# cinch_stereo_ingang.net
KiCad netlist of a schematic drawn in Altium Designer
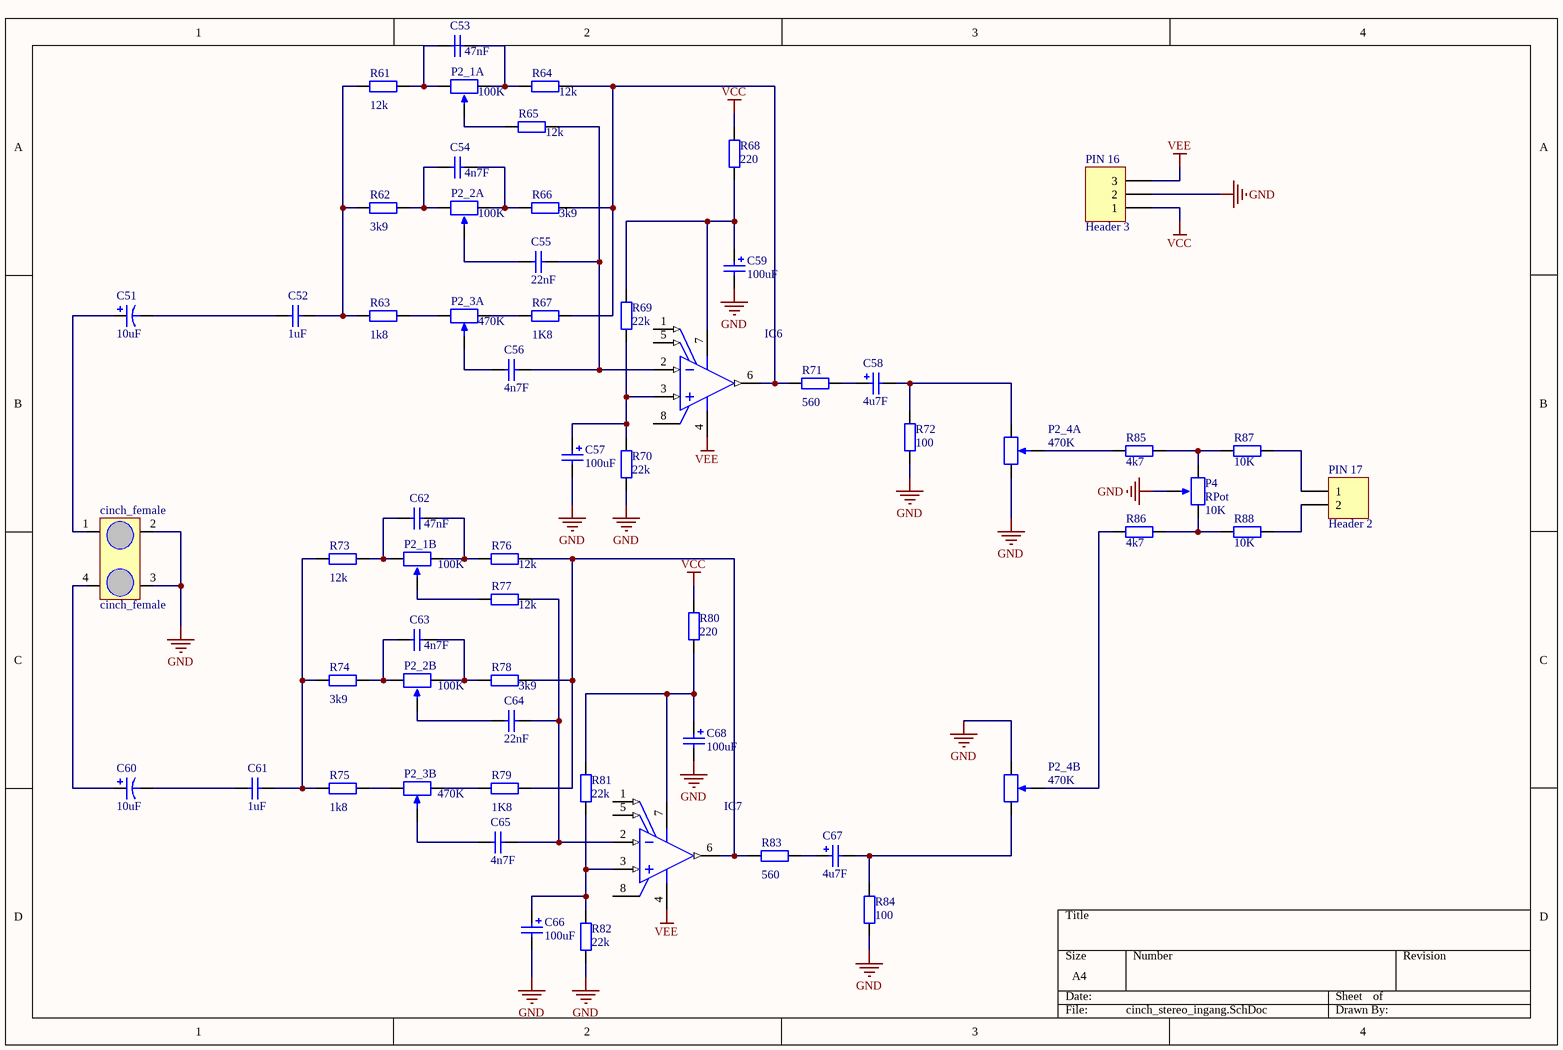
[diagram p0: cinch_stereo_ingang.SchDoc]

(export (version "E")
  (design (tool "Eeschema 10.0.6"))
  (components
    (comp (ref "C51")
      (value "10uF")
      (footprint "Capacitor 10uF")
      (description "electrolytic")
      (fields (field (name "Comment") "Cap Pol2") (field (name "PUBLISHER") "Altium Limited"))
      (libsource (lib "") (part "Cap Pol2_1"))
    )
    (comp (ref "C52")
      (value "1uF")
      (footprint "Capacitor 1uF")
      (description "Capacitor")
      (fields (field (name "Comment") "Cap") (field (name "PUBLISHER") "Altium Limited"))
      (libsource (lib "Autio_Mixer") (part "Cap"))
    )
    (comp (ref "C53")
      (value "47nF")
      (footprint "Capacitor 22nF, 47nF, 100nF")
      (description "Capacitor")
      (fields (field (name "Comment") "Cap") (field (name "PUBLISHER") "Altium Limited"))
      (libsource (lib "Autio_Mixer") (part "Cap"))
    )
    (comp (ref "C54")
      (value "4n7F")
      (footprint "Capacitor 22nF, 47nF, 100nF")
      (description "Capacitor")
      (fields (field (name "Comment") "Cap") (field (name "PUBLISHER") "Altium Limited"))
      (libsource (lib "Autio_Mixer") (part "Cap"))
    )
    (comp (ref "C55")
      (value "22nF")
      (footprint "Capacitor 22nF, 47nF, 100nF")
      (description "Capacitor")
      (fields (field (name "Comment") "Cap") (field (name "PUBLISHER") "Altium Limited"))
      (libsource (lib "Autio_Mixer") (part "Cap"))
    )
    (comp (ref "C56")
      (value "4n7F")
      (footprint "Capacitor 22nF, 47nF, 100nF")
      (description "Capacitor")
      (fields (field (name "Comment") "Cap") (field (name "PUBLISHER") "Altium Limited"))
      (libsource (lib "Autio_Mixer") (part "Cap"))
    )
    (comp (ref "C57")
      (value "100uF")
      (footprint "Capacitor 100uF")
      (description "electrolytic")
      (fields (field (name "Comment") "Cap Pol2") (field (name "PUBLISHER") "Altium Limited"))
      (libsource (lib "Autio_Mixer") (part "Cap Pol2"))
    )
    (comp (ref "C58")
      (value "4u7F")
      (footprint "Capacitor 4u7F")
      (description "electrolytic")
      (fields (field (name "Comment") "Cap Pol2") (field (name "PUBLISHER") "Altium Limited"))
      (libsource (lib "Autio_Mixer") (part "Cap Pol2"))
    )
    (comp (ref "C59")
      (value "100uF")
      (footprint "Capacitor 100uF")
      (description "electrolytic")
      (fields (field (name "Comment") "Cap Pol2") (field (name "PUBLISHER") "Altium Limited"))
      (libsource (lib "Autio_Mixer") (part "Cap Pol2"))
    )
    (comp (ref "C60")
      (value "10uF")
      (footprint "Capacitor 10uF")
      (description "electrolytic")
      (fields (field (name "Comment") "Cap Pol2") (field (name "PUBLISHER") "Altium Limited"))
      (libsource (lib "") (part "Cap Pol2_1"))
    )
    (comp (ref "C61")
      (value "1uF")
      (footprint "Capacitor 1uF")
      (description "Capacitor")
      (fields (field (name "Comment") "Cap") (field (name "PUBLISHER") "Altium Limited"))
      (libsource (lib "Autio_Mixer") (part "Cap"))
    )
    (comp (ref "C62")
      (value "47nF")
      (footprint "Capacitor 22nF, 47nF, 100nF")
      (description "Capacitor")
      (fields (field (name "Comment") "Cap") (field (name "PUBLISHER") "Altium Limited"))
      (libsource (lib "Autio_Mixer") (part "Cap"))
    )
    (comp (ref "C63")
      (value "4n7F")
      (footprint "Capacitor 22nF, 47nF, 100nF")
      (description "Capacitor")
      (fields (field (name "Comment") "Cap") (field (name "PUBLISHER") "Altium Limited"))
      (libsource (lib "Autio_Mixer") (part "Cap"))
    )
    (comp (ref "C64")
      (value "22nF")
      (footprint "Capacitor 22nF, 47nF, 100nF")
      (description "Capacitor")
      (fields (field (name "Comment") "Cap") (field (name "PUBLISHER") "Altium Limited"))
      (libsource (lib "Autio_Mixer") (part "Cap"))
    )
    (comp (ref "C65")
      (value "4n7F")
      (footprint "Capacitor 22nF, 47nF, 100nF")
      (description "Capacitor")
      (fields (field (name "Comment") "Cap") (field (name "PUBLISHER") "Altium Limited"))
      (libsource (lib "Autio_Mixer") (part "Cap"))
    )
    (comp (ref "C66")
      (value "100uF")
      (footprint "Capacitor 100uF")
      (description "electrolytic")
      (fields (field (name "Comment") "Cap Pol2") (field (name "PUBLISHER") "Altium Limited"))
      (libsource (lib "Autio_Mixer") (part "Cap Pol2"))
    )
    (comp (ref "C67")
      (value "4u7F")
      (footprint "Capacitor 4u7F")
      (description "electrolytic")
      (fields (field (name "Comment") "Cap Pol2") (field (name "PUBLISHER") "Altium Limited"))
      (libsource (lib "Autio_Mixer") (part "Cap Pol2"))
    )
    (comp (ref "C68")
      (value "100uF")
      (footprint "Capacitor 100uF")
      (description "electrolytic")
      (fields (field (name "Comment") "Cap Pol2") (field (name "PUBLISHER") "Altium Limited"))
      (libsource (lib "Autio_Mixer") (part "Cap Pol2"))
    )
    (comp (ref "cinch_female")
      (value "cinch_female")
      (footprint "header_4")
      (libsource (lib "Autio_Mixer") (part "cinch_female"))
    )
    (comp (ref "IC6")
      (value "TL061CD")
      (footprint "OPAMP_TL061")
      (fields (field (name "MANUFACTURER") "Texas Instruments"))
      (libsource (lib "Autio_Mixer") (part "opamp_TL061"))
    )
    (comp (ref "IC7")
      (value "TL061CD")
      (footprint "OPAMP_TL061")
      (fields (field (name "MANUFACTURER") "Texas Instruments"))
      (libsource (lib "Autio_Mixer") (part "opamp_TL061"))
    )
    (comp (ref "P2_1A")
      (value "100K")
      (footprint "header_3")
      (description "Potentiometer")
      (fields (field (name "Comment") "RPot") (field (name "PUBLISHER") "Altium Limited"))
      (libsource (lib "Autio_Mixer") (part "RPot"))
    )
    (comp (ref "P2_1B")
      (value "100K")
      (footprint "header_3")
      (description "Potentiometer")
      (fields (field (name "Comment") "RPot") (field (name "PUBLISHER") "Altium Limited"))
      (libsource (lib "Autio_Mixer") (part "RPot"))
    )
    (comp (ref "P2_2A")
      (value "100K")
      (footprint "header_3")
      (description "Potentiometer")
      (fields (field (name "Comment") "RPot") (field (name "PUBLISHER") "Altium Limited"))
      (libsource (lib "Autio_Mixer") (part "RPot"))
    )
    (comp (ref "P2_2B")
      (value "100K")
      (footprint "header_3")
      (description "Potentiometer")
      (fields (field (name "Comment") "RPot") (field (name "PUBLISHER") "Altium Limited"))
      (libsource (lib "Autio_Mixer") (part "RPot"))
    )
    (comp (ref "P2_3A")
      (value "470K")
      (footprint "header_3")
      (description "Potentiometer")
      (fields (field (name "Comment") "RPot") (field (name "PUBLISHER") "Altium Limited"))
      (libsource (lib "") (part "RPot_1_1"))
    )
    (comp (ref "P2_3B")
      (value "470K")
      (footprint "header_3")
      (description "Potentiometer")
      (fields (field (name "Comment") "RPot") (field (name "PUBLISHER") "Altium Limited"))
      (libsource (lib "") (part "RPot_1_1"))
    )
    (comp (ref "P2_4A")
      (value "470K")
      (footprint "header_3")
      (description "Potentiometer")
      (fields (field (name "Comment") "RPot") (field (name "PUBLISHER") "Altium Limited"))
      (libsource (lib "") (part "RPot_1_2"))
    )
    (comp (ref "P2_4B")
      (value "470K")
      (footprint "header_3")
      (description "Potentiometer")
      (fields (field (name "Comment") "RPot") (field (name "PUBLISHER") "Altium Limited"))
      (libsource (lib "Autio_Mixer") (part "RPot_1"))
    )
    (comp (ref "P4")
      (value "RPot")
      (footprint "header_3")
      (description "Potentiometer")
      (fields (field (name "ALTIUM_VALUE") "10K") (field (name "PUBLISHER") "Altium Limited"))
      (libsource (lib "") (part "RPot_1"))
    )
    (comp (ref "PIN 16")
      (value "Header 3")
      (footprint "header_3")
      (description "Header, 3-Pin")
      (fields (field (name "PUBLISHER") "Altium Limited"))
      (libsource (lib "Miscellaneous Connectors") (part "Header 3"))
    )
    (comp (ref "PIN 17")
      (value "Header 2")
      (footprint "header_2")
      (description "Header, 2-Pin")
      (fields (field (name "PUBLISHER") "Altium Limited"))
      (libsource (lib "Miscellaneous Connectors") (part "Header 2"))
    )
    (comp (ref "R61")
      (value "12k")
      (footprint "C1206")
      (description "Resistor")
      (fields (field (name "Comment") "Res2") (field (name "PUBLISHER") "Altium Limited"))
      (libsource (lib "") (part "Res2_1"))
    )
    (comp (ref "R62")
      (value "3k9")
      (footprint "C1206")
      (description "Resistor")
      (fields (field (name "Comment") "Res2") (field (name "PUBLISHER") "Altium Limited"))
      (libsource (lib "") (part "Res2_1"))
    )
    (comp (ref "R63")
      (value "1k8")
      (footprint "C1206")
      (description "Resistor")
      (fields (field (name "Comment") "Res2") (field (name "PUBLISHER") "Altium Limited"))
      (libsource (lib "") (part "Res2_1"))
    )
    (comp (ref "R64")
      (value "12k")
      (footprint "C1206")
      (description "Resistor")
      (fields (field (name "Comment") "Res2") (field (name "PUBLISHER") "Altium Limited"))
      (libsource (lib "") (part "Res2_1"))
    )
    (comp (ref "R65")
      (value "12k")
      (footprint "C1206")
      (description "Resistor")
      (fields (field (name "Comment") "Res2") (field (name "PUBLISHER") "Altium Limited"))
      (libsource (lib "") (part "Res2_1"))
    )
    (comp (ref "R66")
      (value "3k9")
      (footprint "C1206")
      (description "Resistor")
      (fields (field (name "Comment") "Res2") (field (name "PUBLISHER") "Altium Limited"))
      (libsource (lib "") (part "Res2_1"))
    )
    (comp (ref "R67")
      (value "1K8")
      (footprint "C1206")
      (description "Resistor")
      (fields (field (name "Comment") "Res2") (field (name "PUBLISHER") "Altium Limited"))
      (libsource (lib "") (part "Res2_1"))
    )
    (comp (ref "R68")
      (value "220")
      (footprint "C1206")
      (description "Resistor")
      (fields (field (name "Comment") "Res2") (field (name "PUBLISHER") "Altium Limited"))
      (libsource (lib "Miscellaneous Devices") (part "Res2"))
    )
    (comp (ref "R69")
      (value "22k")
      (footprint "C1206")
      (description "Resistor")
      (fields (field (name "Comment") "Res2") (field (name "PUBLISHER") "Altium Limited"))
      (libsource (lib "Miscellaneous Devices") (part "Res2"))
    )
    (comp (ref "R70")
      (value "22k")
      (footprint "C1206")
      (description "Resistor")
      (fields (field (name "Comment") "Res2") (field (name "PUBLISHER") "Altium Limited"))
      (libsource (lib "Miscellaneous Devices") (part "Res2"))
    )
    (comp (ref "R71")
      (value "560")
      (footprint "C1206")
      (description "Resistor")
      (fields (field (name "Comment") "Res2") (field (name "PUBLISHER") "Altium Limited"))
      (libsource (lib "") (part "Res2_1"))
    )
    (comp (ref "R72")
      (value "100")
      (footprint "C1206")
      (description "Resistor")
      (fields (field (name "Comment") "Res2") (field (name "PUBLISHER") "Altium Limited"))
      (libsource (lib "Miscellaneous Devices") (part "Res2"))
    )
    (comp (ref "R73")
      (value "12k")
      (footprint "C1206")
      (description "Resistor")
      (fields (field (name "Comment") "Res2") (field (name "PUBLISHER") "Altium Limited"))
      (libsource (lib "") (part "Res2_1"))
    )
    (comp (ref "R74")
      (value "3k9")
      (footprint "C1206")
      (description "Resistor")
      (fields (field (name "Comment") "Res2") (field (name "PUBLISHER") "Altium Limited"))
      (libsource (lib "") (part "Res2_1"))
    )
    (comp (ref "R75")
      (value "1k8")
      (footprint "C1206")
      (description "Resistor")
      (fields (field (name "Comment") "Res2") (field (name "PUBLISHER") "Altium Limited"))
      (libsource (lib "") (part "Res2_1"))
    )
    (comp (ref "R76")
      (value "12k")
      (footprint "C1206")
      (description "Resistor")
      (fields (field (name "Comment") "Res2") (field (name "PUBLISHER") "Altium Limited"))
      (libsource (lib "") (part "Res2_1"))
    )
    (comp (ref "R77")
      (value "12k")
      (footprint "C1206")
      (description "Resistor")
      (fields (field (name "Comment") "Res2") (field (name "PUBLISHER") "Altium Limited"))
      (libsource (lib "") (part "Res2_1"))
    )
    (comp (ref "R78")
      (value "3k9")
      (footprint "C1206")
      (description "Resistor")
      (fields (field (name "Comment") "Res2") (field (name "PUBLISHER") "Altium Limited"))
      (libsource (lib "") (part "Res2_1"))
    )
    (comp (ref "R79")
      (value "1K8")
      (footprint "C1206")
      (description "Resistor")
      (fields (field (name "Comment") "Res2") (field (name "PUBLISHER") "Altium Limited"))
      (libsource (lib "") (part "Res2_1"))
    )
    (comp (ref "R80")
      (value "220")
      (footprint "C1206")
      (description "Resistor")
      (fields (field (name "Comment") "Res2") (field (name "PUBLISHER") "Altium Limited"))
      (libsource (lib "Miscellaneous Devices") (part "Res2"))
    )
    (comp (ref "R81")
      (value "22k")
      (footprint "C1206")
      (description "Resistor")
      (fields (field (name "Comment") "Res2") (field (name "PUBLISHER") "Altium Limited"))
      (libsource (lib "Miscellaneous Devices") (part "Res2"))
    )
    (comp (ref "R82")
      (value "22k")
      (footprint "C1206")
      (description "Resistor")
      (fields (field (name "Comment") "Res2") (field (name "PUBLISHER") "Altium Limited"))
      (libsource (lib "Miscellaneous Devices") (part "Res2"))
    )
    (comp (ref "R83")
      (value "560")
      (footprint "C1206")
      (description "Resistor")
      (fields (field (name "Comment") "Res2") (field (name "PUBLISHER") "Altium Limited"))
      (libsource (lib "") (part "Res2_1"))
    )
    (comp (ref "R84")
      (value "100")
      (footprint "C1206")
      (description "Resistor")
      (fields (field (name "Comment") "Res2") (field (name "PUBLISHER") "Altium Limited"))
      (libsource (lib "Miscellaneous Devices") (part "Res2"))
    )
    (comp (ref "R85")
      (value "4k7")
      (footprint "C1206")
      (description "Resistor")
      (fields (field (name "Comment") "Res2") (field (name "PUBLISHER") "Altium Limited"))
      (libsource (lib "Autio_Mixer") (part "Res2_13"))
    )
    (comp (ref "R86")
      (value "4k7")
      (footprint "C1206")
      (description "Resistor")
      (fields (field (name "Comment") "Res2") (field (name "PUBLISHER") "Altium Limited"))
      (libsource (lib "Autio_Mixer") (part "Res2_13"))
    )
    (comp (ref "R87")
      (value "10K")
      (footprint "C1206")
      (description "Resistor")
      (fields (field (name "Comment") "Res2") (field (name "PUBLISHER") "Altium Limited"))
      (libsource (lib "Autio_Mixer") (part "Res2_3"))
    )
    (comp (ref "R88")
      (value "10K")
      (footprint "C1206")
      (description "Resistor")
      (fields (field (name "Comment") "Res2") (field (name "PUBLISHER") "Altium Limited"))
      (libsource (lib "Autio_Mixer") (part "Res2_3"))
    )
  )
  (nets
    (net (code "1") (name "GND") (class "Default")
      (node (ref "C57") (pin "2") (pinfunction "2_2") (pintype "passive"))
      (node (ref "C59") (pin "2") (pinfunction "2_2") (pintype "passive"))
      (node (ref "C66") (pin "2") (pinfunction "2_2") (pintype "passive"))
      (node (ref "C68") (pin "2") (pinfunction "2_2") (pintype "passive"))
      (node (ref "P2_4A") (pin "3") (pinfunction "TOP_3") (pintype "passive"))
      (node (ref "P2_4B") (pin "3") (pinfunction "BOT_3") (pintype "passive"))
      (node (ref "P4") (pin "3") (pinfunction "TAP_3") (pintype "passive"))
      (node (ref "PIN 16") (pin "3") (pinfunction "2_3") (pintype "passive"))
      (node (ref "R70") (pin "1") (pinfunction "1_1") (pintype "passive"))
      (node (ref "R72") (pin "1") (pinfunction "1_1") (pintype "passive"))
      (node (ref "R82") (pin "1") (pinfunction "1_1") (pintype "passive"))
      (node (ref "R84") (pin "1") (pinfunction "1_1") (pintype "passive"))
      (node (ref "cinch_female") (pin "2") (pinfunction "GND_left_2") (pintype "passive"))
      (node (ref "cinch_female") (pin "3") (pinfunction "GND_right_3") (pintype "passive"))
    )
    (net (code "2") (name "Net-(C51-Pad2)") (class "Default")
      (node (ref "C51") (pin "2") (pinfunction "2_2") (pintype "passive"))
      (node (ref "C52") (pin "1") (pinfunction "1_1") (pintype "passive"))
    )
    (net (code "3") (name "Net-(C52-Pad2)") (class "Default")
      (node (ref "C52") (pin "2") (pinfunction "2_2") (pintype "passive"))
      (node (ref "R61") (pin "1") (pinfunction "1_1") (pintype "passive"))
      (node (ref "R62") (pin "1") (pinfunction "1_1") (pintype "passive"))
      (node (ref "R63") (pin "1") (pinfunction "1_1") (pintype "passive"))
    )
    (net (code "4") (name "Net-(C58-Pad1)") (class "Default")
      (node (ref "C58") (pin "1") (pinfunction "1_1") (pintype "passive"))
      (node (ref "R71") (pin "2") (pinfunction "2_2") (pintype "passive"))
    )
    (net (code "5") (name "Net-(C60-Pad2)") (class "Default")
      (node (ref "C60") (pin "2") (pinfunction "2_2") (pintype "passive"))
      (node (ref "C61") (pin "1") (pinfunction "1_1") (pintype "passive"))
    )
    (net (code "6") (name "Net-(C61-Pad2)") (class "Default")
      (node (ref "C61") (pin "2") (pinfunction "2_2") (pintype "passive"))
      (node (ref "R73") (pin "1") (pinfunction "1_1") (pintype "passive"))
      (node (ref "R74") (pin "1") (pinfunction "1_1") (pintype "passive"))
      (node (ref "R75") (pin "1") (pinfunction "1_1") (pintype "passive"))
    )
    (net (code "7") (name "Net-(C67-Pad1)") (class "Default")
      (node (ref "C67") (pin "1") (pinfunction "1_1") (pintype "passive"))
      (node (ref "R83") (pin "2") (pinfunction "2_2") (pintype "passive"))
    )
    (net (code "8") (name "Net-(IC6-IN+)") (class "Default")
      (node (ref "C57") (pin "1") (pinfunction "1_1") (pintype "passive"))
      (node (ref "IC6") (pin "3") (pinfunction "IN+_3") (pintype "input"))
      (node (ref "R69") (pin "1") (pinfunction "1_1") (pintype "passive"))
      (node (ref "R70") (pin "2") (pinfunction "2_2") (pintype "passive"))
    )
    (net (code "9") (name "Net-(IC6-IN-)") (class "Default")
      (node (ref "C55") (pin "2") (pinfunction "2_2") (pintype "passive"))
      (node (ref "C56") (pin "2") (pinfunction "2_2") (pintype "passive"))
      (node (ref "IC6") (pin "2") (pinfunction "IN-_2") (pintype "input"))
      (node (ref "R65") (pin "2") (pinfunction "2_2") (pintype "passive"))
    )
    (net (code "10") (name "Net-(IC6-OUT)") (class "Default")
      (node (ref "IC6") (pin "6") (pinfunction "OUT_6") (pintype "output"))
      (node (ref "R64") (pin "2") (pinfunction "2_2") (pintype "passive"))
      (node (ref "R66") (pin "2") (pinfunction "2_2") (pintype "passive"))
      (node (ref "R67") (pin "2") (pinfunction "2_2") (pintype "passive"))
      (node (ref "R71") (pin "1") (pinfunction "1_1") (pintype "passive"))
    )
    (net (code "11") (name "Net-(IC6-VCC+)") (class "Default")
      (node (ref "C59") (pin "1") (pinfunction "1_1") (pintype "passive"))
      (node (ref "IC6") (pin "7") (pinfunction "VCC+_7") (pintype "power_in"))
      (node (ref "R68") (pin "1") (pinfunction "1_1") (pintype "passive"))
      (node (ref "R69") (pin "2") (pinfunction "2_2") (pintype "passive"))
    )
    (net (code "12") (name "Net-(IC7-IN+)") (class "Default")
      (node (ref "C66") (pin "1") (pinfunction "1_1") (pintype "passive"))
      (node (ref "IC7") (pin "3") (pinfunction "IN+_3") (pintype "input"))
      (node (ref "R81") (pin "1") (pinfunction "1_1") (pintype "passive"))
      (node (ref "R82") (pin "2") (pinfunction "2_2") (pintype "passive"))
    )
    (net (code "13") (name "Net-(IC7-IN-)") (class "Default")
      (node (ref "C64") (pin "2") (pinfunction "2_2") (pintype "passive"))
      (node (ref "C65") (pin "2") (pinfunction "2_2") (pintype "passive"))
      (node (ref "IC7") (pin "2") (pinfunction "IN-_2") (pintype "input"))
      (node (ref "R77") (pin "2") (pinfunction "2_2") (pintype "passive"))
    )
    (net (code "14") (name "Net-(IC7-OUT)") (class "Default")
      (node (ref "IC7") (pin "6") (pinfunction "OUT_6") (pintype "output"))
      (node (ref "R76") (pin "2") (pinfunction "2_2") (pintype "passive"))
      (node (ref "R78") (pin "2") (pinfunction "2_2") (pintype "passive"))
      (node (ref "R79") (pin "2") (pinfunction "2_2") (pintype "passive"))
      (node (ref "R83") (pin "1") (pinfunction "1_1") (pintype "passive"))
    )
    (net (code "15") (name "Net-(IC7-VCC+)") (class "Default")
      (node (ref "C68") (pin "1") (pinfunction "1_1") (pintype "passive"))
      (node (ref "IC7") (pin "7") (pinfunction "VCC+_7") (pintype "power_in"))
      (node (ref "R80") (pin "1") (pinfunction "1_1") (pintype "passive"))
      (node (ref "R81") (pin "2") (pinfunction "2_2") (pintype "passive"))
    )
    (net (code "16") (name "Net-(P2_1A-BOT)") (class "Default")
      (node (ref "C53") (pin "2") (pinfunction "2_2") (pintype "passive"))
      (node (ref "P2_1A") (pin "3") (pinfunction "BOT_3") (pintype "passive"))
      (node (ref "R64") (pin "1") (pinfunction "1_1") (pintype "passive"))
    )
    (net (code "17") (name "Net-(P2_1A-TAP)") (class "Default")
      (node (ref "P2_1A") (pin "2") (pinfunction "TAP_2") (pintype "passive"))
      (node (ref "R65") (pin "1") (pinfunction "1_1") (pintype "passive"))
    )
    (net (code "18") (name "Net-(P2_1A-TOP)") (class "Default")
      (node (ref "C53") (pin "1") (pinfunction "1_1") (pintype "passive"))
      (node (ref "P2_1A") (pin "1") (pinfunction "TOP_1") (pintype "passive"))
      (node (ref "R61") (pin "2") (pinfunction "2_2") (pintype "passive"))
    )
    (net (code "19") (name "Net-(P2_1B-BOT)") (class "Default")
      (node (ref "C62") (pin "2") (pinfunction "2_2") (pintype "passive"))
      (node (ref "P2_1B") (pin "3") (pinfunction "BOT_3") (pintype "passive"))
      (node (ref "R76") (pin "1") (pinfunction "1_1") (pintype "passive"))
    )
    (net (code "20") (name "Net-(P2_1B-TAP)") (class "Default")
      (node (ref "P2_1B") (pin "2") (pinfunction "TAP_2") (pintype "passive"))
      (node (ref "R77") (pin "1") (pinfunction "1_1") (pintype "passive"))
    )
    (net (code "21") (name "Net-(P2_1B-TOP)") (class "Default")
      (node (ref "C62") (pin "1") (pinfunction "1_1") (pintype "passive"))
      (node (ref "P2_1B") (pin "1") (pinfunction "TOP_1") (pintype "passive"))
      (node (ref "R73") (pin "2") (pinfunction "2_2") (pintype "passive"))
    )
    (net (code "22") (name "Net-(P2_2A-BOT)") (class "Default")
      (node (ref "C54") (pin "2") (pinfunction "2_2") (pintype "passive"))
      (node (ref "P2_2A") (pin "3") (pinfunction "BOT_3") (pintype "passive"))
      (node (ref "R66") (pin "1") (pinfunction "1_1") (pintype "passive"))
    )
    (net (code "23") (name "Net-(P2_2A-TAP)") (class "Default")
      (node (ref "C55") (pin "1") (pinfunction "1_1") (pintype "passive"))
      (node (ref "P2_2A") (pin "2") (pinfunction "TAP_2") (pintype "passive"))
    )
    (net (code "24") (name "Net-(P2_2A-TOP)") (class "Default")
      (node (ref "C54") (pin "1") (pinfunction "1_1") (pintype "passive"))
      (node (ref "P2_2A") (pin "1") (pinfunction "TOP_1") (pintype "passive"))
      (node (ref "R62") (pin "2") (pinfunction "2_2") (pintype "passive"))
    )
    (net (code "25") (name "Net-(P2_2B-BOT)") (class "Default")
      (node (ref "C63") (pin "2") (pinfunction "2_2") (pintype "passive"))
      (node (ref "P2_2B") (pin "3") (pinfunction "BOT_3") (pintype "passive"))
      (node (ref "R78") (pin "1") (pinfunction "1_1") (pintype "passive"))
    )
    (net (code "26") (name "Net-(P2_2B-TAP)") (class "Default")
      (node (ref "C64") (pin "1") (pinfunction "1_1") (pintype "passive"))
      (node (ref "P2_2B") (pin "2") (pinfunction "TAP_2") (pintype "passive"))
    )
    (net (code "27") (name "Net-(P2_2B-TOP)") (class "Default")
      (node (ref "C63") (pin "1") (pinfunction "1_1") (pintype "passive"))
      (node (ref "P2_2B") (pin "1") (pinfunction "TOP_1") (pintype "passive"))
      (node (ref "R74") (pin "2") (pinfunction "2_2") (pintype "passive"))
    )
    (net (code "28") (name "Net-(P2_3A-BOT)") (class "Default")
      (node (ref "P2_3A") (pin "3") (pinfunction "BOT_3") (pintype "passive"))
      (node (ref "R67") (pin "1") (pinfunction "1_1") (pintype "passive"))
    )
    (net (code "29") (name "Net-(P2_3A-TAP)") (class "Default")
      (node (ref "C56") (pin "1") (pinfunction "1_1") (pintype "passive"))
      (node (ref "P2_3A") (pin "2") (pinfunction "TAP_2") (pintype "passive"))
    )
    (net (code "30") (name "Net-(P2_3A-TOP)") (class "Default")
      (node (ref "P2_3A") (pin "1") (pinfunction "TOP_1") (pintype "passive"))
      (node (ref "R63") (pin "2") (pinfunction "2_2") (pintype "passive"))
    )
    (net (code "31") (name "Net-(P2_3B-BOT)") (class "Default")
      (node (ref "P2_3B") (pin "3") (pinfunction "BOT_3") (pintype "passive"))
      (node (ref "R79") (pin "1") (pinfunction "1_1") (pintype "passive"))
    )
    (net (code "32") (name "Net-(P2_3B-TAP)") (class "Default")
      (node (ref "C65") (pin "1") (pinfunction "1_1") (pintype "passive"))
      (node (ref "P2_3B") (pin "2") (pinfunction "TAP_2") (pintype "passive"))
    )
    (net (code "33") (name "Net-(P2_3B-TOP)") (class "Default")
      (node (ref "P2_3B") (pin "1") (pinfunction "TOP_1") (pintype "passive"))
      (node (ref "R75") (pin "2") (pinfunction "2_2") (pintype "passive"))
    )
    (net (code "34") (name "Net-(P2_4A-BOT)") (class "Default")
      (node (ref "C58") (pin "2") (pinfunction "2_2") (pintype "passive"))
      (node (ref "P2_4A") (pin "1") (pinfunction "BOT_1") (pintype "passive"))
      (node (ref "R72") (pin "2") (pinfunction "2_2") (pintype "passive"))
    )
    (net (code "35") (name "Net-(P2_4A-TAP)") (class "Default")
      (node (ref "P2_4A") (pin "2") (pinfunction "TAP_2") (pintype "passive"))
      (node (ref "R85") (pin "1") (pinfunction "1_1") (pintype "passive"))
    )
    (net (code "36") (name "Net-(P2_4B-TAP)") (class "Default")
      (node (ref "P2_4B") (pin "2") (pinfunction "TAP_2") (pintype "passive"))
      (node (ref "R86") (pin "1") (pinfunction "1_1") (pintype "passive"))
    )
    (net (code "37") (name "Net-(P2_4B-TOP)") (class "Default")
      (node (ref "C67") (pin "2") (pinfunction "2_2") (pintype "passive"))
      (node (ref "P2_4B") (pin "1") (pinfunction "TOP_1") (pintype "passive"))
      (node (ref "R84") (pin "2") (pinfunction "2_2") (pintype "passive"))
    )
    (net (code "38") (name "Net-(P4-BOT)") (class "Default")
      (node (ref "P4") (pin "1") (pinfunction "BOT_1") (pintype "passive"))
      (node (ref "R86") (pin "2") (pinfunction "2_2") (pintype "passive"))
      (node (ref "R88") (pin "1") (pinfunction "1_1") (pintype "passive"))
    )
    (net (code "39") (name "Net-(P4-TOP)") (class "Default")
      (node (ref "P4") (pin "2") (pinfunction "TOP_2") (pintype "passive"))
      (node (ref "R85") (pin "2") (pinfunction "2_2") (pintype "passive"))
      (node (ref "R87") (pin "1") (pinfunction "1_1") (pintype "passive"))
    )
    (net (code "40") (name "Net-(PIN 17-Pad1)") (class "Default")
      (node (ref "PIN 17") (pin "1") (pinfunction "1_1") (pintype "passive"))
      (node (ref "R87") (pin "2") (pinfunction "2_2") (pintype "passive"))
    )
    (net (code "41") (name "Net-(PIN 17-Pad2)") (class "Default")
      (node (ref "PIN 17") (pin "2") (pinfunction "2_2") (pintype "passive"))
      (node (ref "R88") (pin "2") (pinfunction "2_2") (pintype "passive"))
    )
    (net (code "42") (name "Net-(cinch_female-Left_red)") (class "Default")
      (node (ref "C51") (pin "1") (pinfunction "1_1") (pintype "passive"))
      (node (ref "cinch_female") (pin "1") (pinfunction "Left_red_1") (pintype "passive"))
    )
    (net (code "43") (name "Net-(cinch_female-Right_Black{slash}White)") (class "Default")
      (node (ref "C60") (pin "1") (pinfunction "1_1") (pintype "passive"))
      (node (ref "cinch_female") (pin "4") (pinfunction "Right_Black/White_4") (pintype "passive"))
    )
    (net (code "44") (name "VCC") (class "Default")
      (node (ref "PIN 16") (pin "2") (pinfunction "1_2") (pintype "passive"))
      (node (ref "R68") (pin "2") (pinfunction "2_2") (pintype "passive"))
      (node (ref "R80") (pin "2") (pinfunction "2_2") (pintype "passive"))
    )
    (net (code "45") (name "VEE") (class "Default")
      (node (ref "IC6") (pin "4") (pinfunction "VCC-_4") (pintype "power_in"))
      (node (ref "IC7") (pin "4") (pinfunction "VCC-_4") (pintype "power_in"))
      (node (ref "PIN 16") (pin "1") (pinfunction "3_1") (pintype "passive"))
    )
    (net (code "46") (name "unconnected-(IC6-NC-Pad8)") (class "Default")
      (node (ref "IC6") (pin "8") (pinfunction "NC_8") (pintype "passive"))
    )
    (net (code "47") (name "unconnected-(IC6-OFFSET_N1-Pad1)") (class "Default")
      (node (ref "IC6") (pin "1") (pinfunction "OFFSET_N1_1") (pintype "input"))
    )
    (net (code "48") (name "unconnected-(IC6-OFFSET_N2-Pad5)") (class "Default")
      (node (ref "IC6") (pin "5") (pinfunction "OFFSET_N2_5") (pintype "input"))
    )
    (net (code "49") (name "unconnected-(IC7-NC-Pad8)") (class "Default")
      (node (ref "IC7") (pin "8") (pinfunction "NC_8") (pintype "passive"))
    )
    (net (code "50") (name "unconnected-(IC7-OFFSET_N1-Pad1)") (class "Default")
      (node (ref "IC7") (pin "1") (pinfunction "OFFSET_N1_1") (pintype "input"))
    )
    (net (code "51") (name "unconnected-(IC7-OFFSET_N2-Pad5)") (class "Default")
      (node (ref "IC7") (pin "5") (pinfunction "OFFSET_N2_5") (pintype "input"))
    )
  )
)
